# ds18b20.net
KiCad netlist of a schematic drawn in Altium Designer
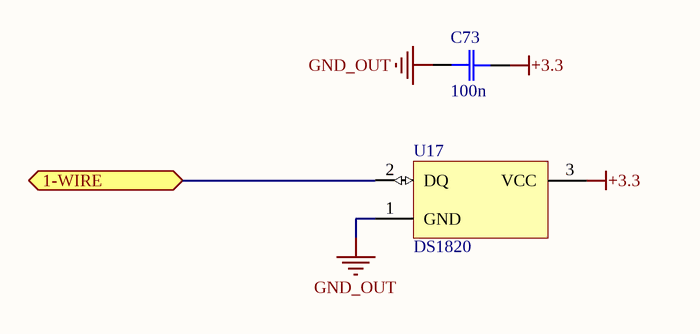
[diagram p0: ds18b20.SchDoc]

(export (version "E")
  (design (tool "Eeschema 10.0.6"))
  (components
    (comp (ref "C73") (value "100n") (footprint "CAP: 0603") (libsource (lib "PASSIVE") (part "C_SMD")))
    (comp (ref "U17")
      (value "DS1820")
      (footprint "PR35")
      (description "1-Wire Digital Thermometer")
      (fields (field (name "PUBLISHER") "Altium Limited"))
      (libsource (lib "Dallas Sensor Temperature Sensor") (part "DS1820"))
    )
  )
  (nets
    (net (code "1") (name "+3.3") (class "Default")
      (node (ref "C73") (pin "1") (pinfunction "1_1") (pintype "passive"))
      (node (ref "U17") (pin "3") (pinfunction "VCC_3") (pintype "power_in"))
    )
    (net (code "2") (name "/1-WIRE") (class "Default")
      (node (ref "U17") (pin "2") (pinfunction "DQ_2") (pintype "bidirectional"))
    )
    (net (code "3") (name "GND_OUT") (class "Default")
      (node (ref "C73") (pin "2") (pinfunction "2_2") (pintype "passive"))
      (node (ref "U17") (pin "1") (pinfunction "GND_1") (pintype "power_in"))
    )
  )
)
